# PAGE4_-_SENSORS.net
KiCad netlist of a schematic drawn in Altium Designer
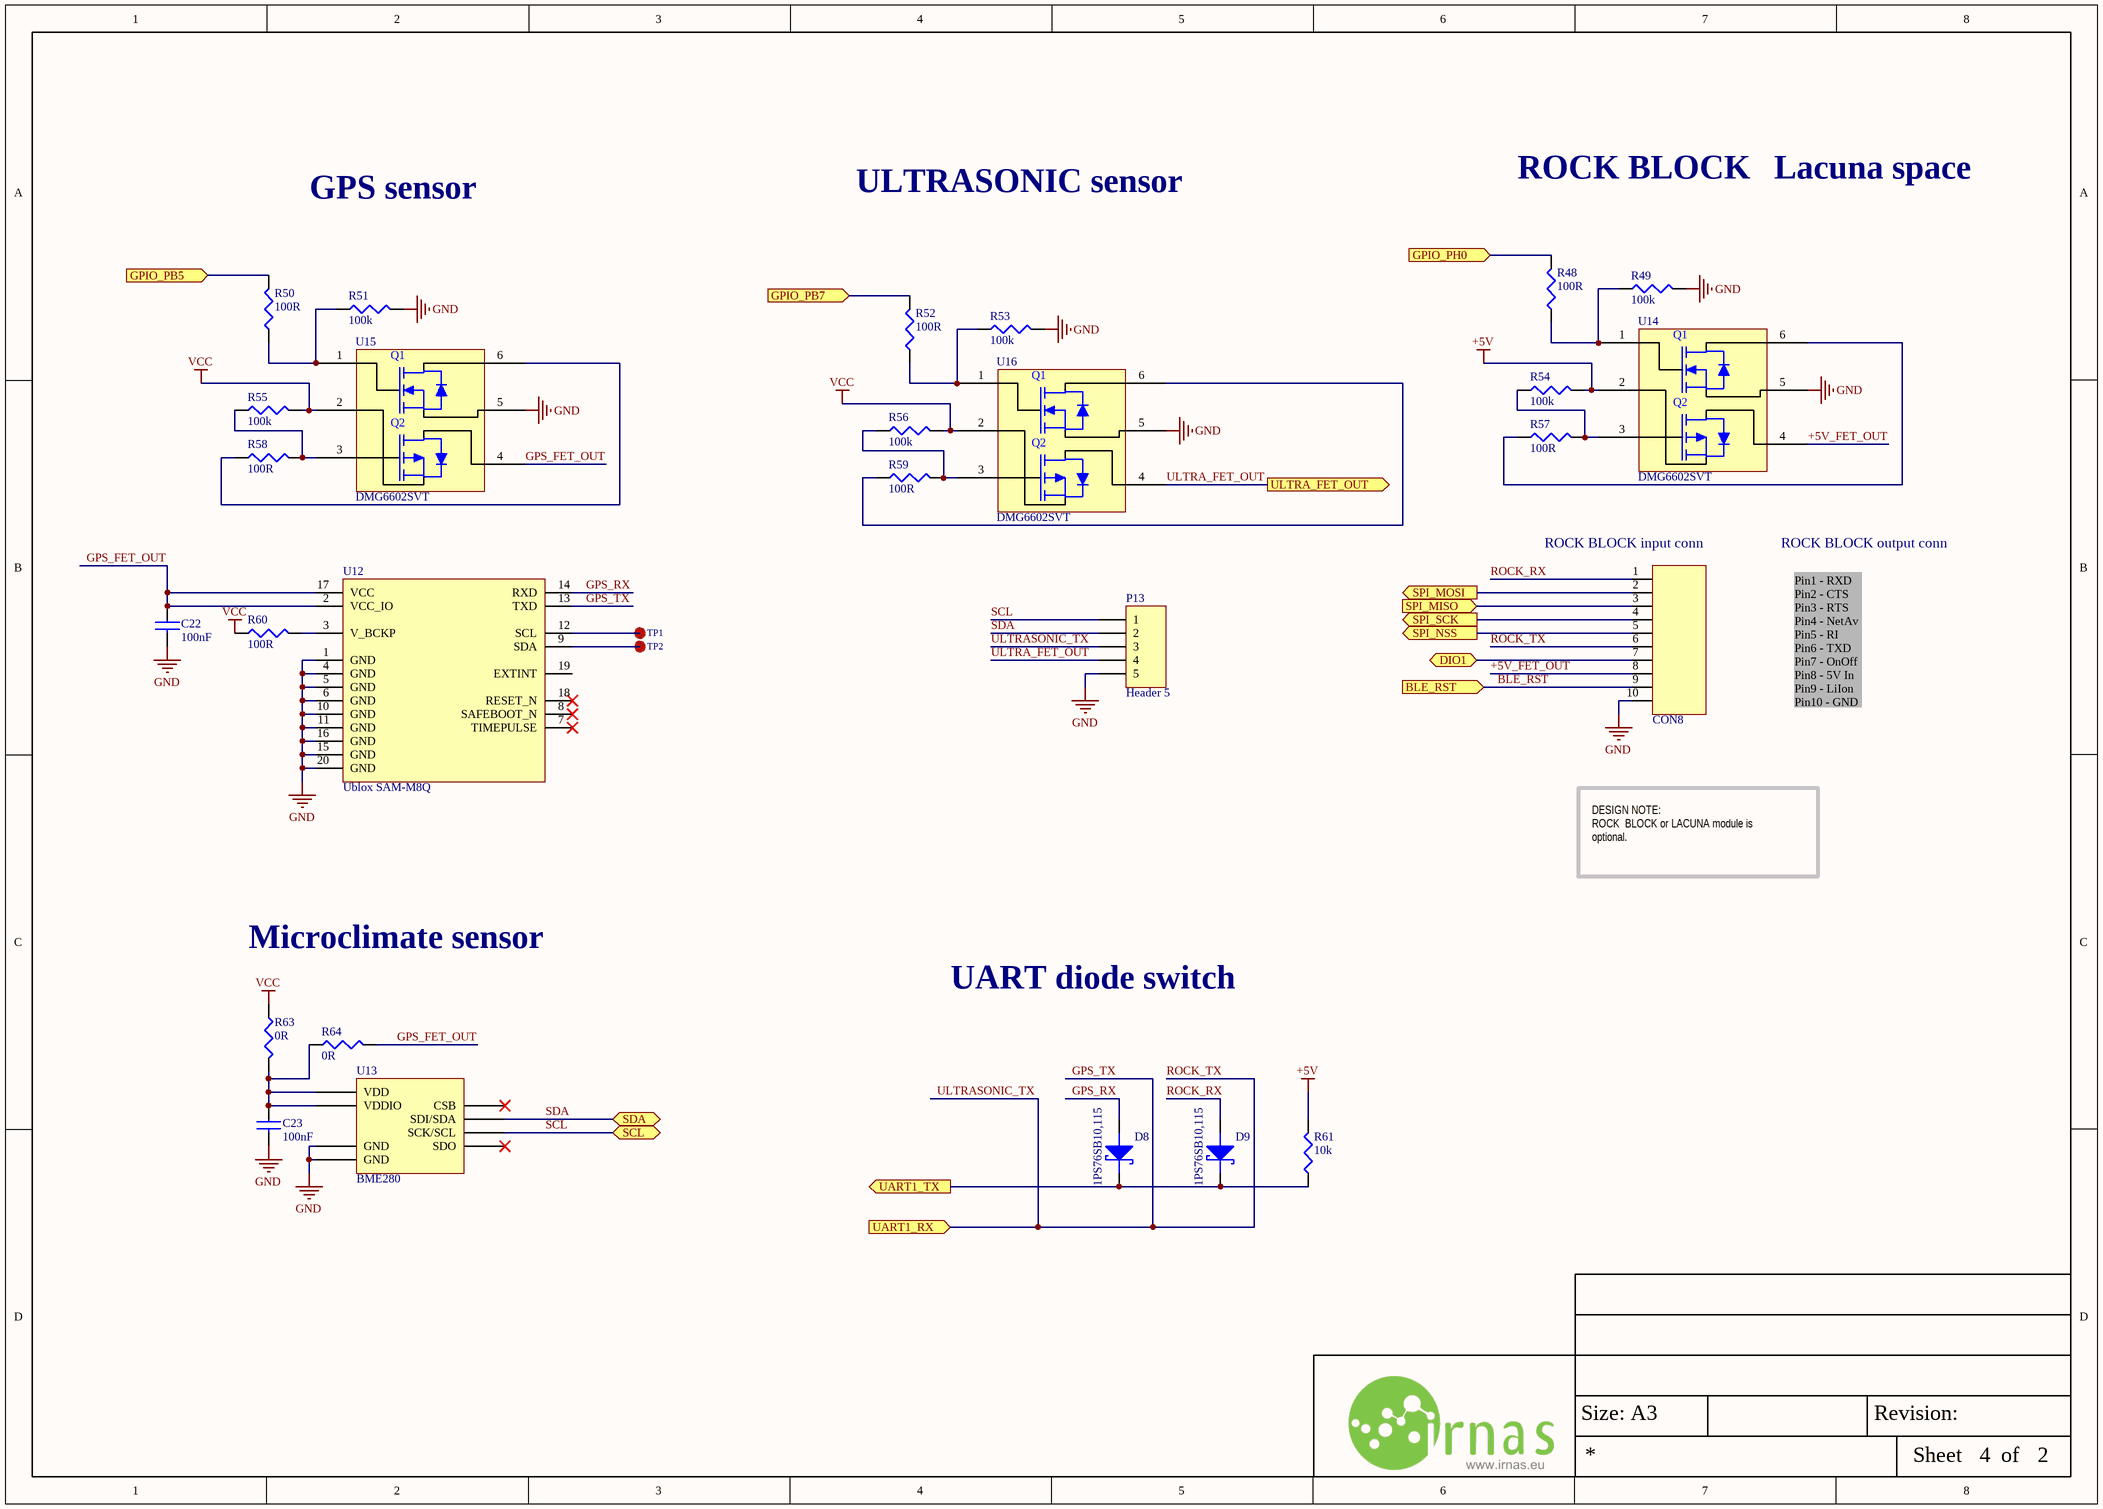
[diagram p0: PAGE4 - SENSORS.SchDoc]

(export (version "E")
  (design (tool "Eeschema 10.0.6"))
  (components
    (comp (ref "C22")
      (value "100nF")
      (footprint "CAP0603")
      (description "MURATA - GRM188R71C104KA01J - CAP, MLCC, X7R, 0.1UF, 16V, 0603")
      (fields
        (field (name "MANUFACTURER") "MURATA")
        (field (name "MANUFACTURER PART NUMBER") "GRM188R71C104KA01J")
      )
      (libsource (lib "Passive") (part "C - 100nF"))
    )
    (comp (ref "C23")
      (value "100nF")
      (footprint "CAP0603")
      (description "MURATA - GRM188R71C104KA01J - CAP, MLCC, X7R, 0.1UF, 16V, 0603")
      (fields
        (field (name "MANUFACTURER") "MURATA")
        (field (name "MANUFACTURER PART NUMBER") "GRM188R71C104KA01J")
      )
      (libsource (lib "Passive") (part "C - 100nF"))
    )
    (comp (ref "CON8")
      (value "53261-1071")
      (footprint "PICOBLADE 10PIN")
      (description "Wire-To-Board Connector, Right Angle, 1.25 mm, 10 Contacts, Header, PicoBlade 53261 Series")
      (libsource (lib "Connectors") (part "PicoBlade 10pin"))
    )
    (comp (ref "D8")
      (value "1PS76SB10,115")
      (footprint "SOD-323")
      (description "Small Signal Schottky Diode, Single, 30 V, 200 mA, 320 mV, 800 mA, 125 °C")
      (libsource (lib "Active") (part "DS - 1PS76SB10,115"))
    )
    (comp (ref "D9")
      (value "1PS76SB10,115")
      (footprint "SOD-323")
      (description "Small Signal Schottky Diode, Single, 30 V, 200 mA, 320 mV, 800 mA, 125 °C")
      (libsource (lib "Active") (part "DS - 1PS76SB10,115"))
    )
    (comp (ref "P13")
      (value "Header 5")
      (footprint "HDR1X5")
      (description "Header, 5-Pin")
      (fields (field (name "PUBLISHER") "Altium Limited"))
      (libsource (lib "Miscellaneous Connectors") (part "Header 5"))
    )
    (comp (ref "R48")
      (value "100R")
      (footprint "RES0603")
      (description "MULTICOMP - MC0063W06031100R - RES, THICK FILM, 100R, 1%, 0.063W, 0603")
      (fields
        (field (name "MANUFACTURER") "MULTICOMP")
        (field (name "MANUFACTURER PART NUMBER") "MC0063W06031100R")
      )
      (libsource (lib "Passive") (part "R - 100R"))
    )
    (comp (ref "R49")
      (value "100k")
      (footprint "RES0603")
      (description "MULTICOMP - MCMR06X104 JTL - RES, CERAMIC, 100K, 5%, 0.1W, 0603")
      (fields
        (field (name "MANUFACTURER") "MULTICOMP")
        (field (name "MANUFACTURER PART NUMBER") "MCMR06X104 JTL")
      )
      (libsource (lib "Passive") (part "R - 100k"))
    )
    (comp (ref "R50")
      (value "100R")
      (footprint "RES0603")
      (description "MULTICOMP - MC0063W06031100R - RES, THICK FILM, 100R, 1%, 0.063W, 0603")
      (fields
        (field (name "MANUFACTURER") "MULTICOMP")
        (field (name "MANUFACTURER PART NUMBER") "MC0063W06031100R")
      )
      (libsource (lib "Passive") (part "R - 100R"))
    )
    (comp (ref "R51")
      (value "100k")
      (footprint "RES0603")
      (description "MULTICOMP - MCMR06X104 JTL - RES, CERAMIC, 100K, 5%, 0.1W, 0603")
      (fields
        (field (name "MANUFACTURER") "MULTICOMP")
        (field (name "MANUFACTURER PART NUMBER") "MCMR06X104 JTL")
      )
      (libsource (lib "Passive") (part "R - 100k"))
    )
    (comp (ref "R52")
      (value "100R")
      (footprint "RES0603")
      (description "MULTICOMP - MC0063W06031100R - RES, THICK FILM, 100R, 1%, 0.063W, 0603")
      (fields
        (field (name "MANUFACTURER") "MULTICOMP")
        (field (name "MANUFACTURER PART NUMBER") "MC0063W06031100R")
      )
      (libsource (lib "Passive") (part "R - 100R"))
    )
    (comp (ref "R53")
      (value "100k")
      (footprint "RES0603")
      (description "MULTICOMP - MCMR06X104 JTL - RES, CERAMIC, 100K, 5%, 0.1W, 0603")
      (fields
        (field (name "MANUFACTURER") "MULTICOMP")
        (field (name "MANUFACTURER PART NUMBER") "MCMR06X104 JTL")
      )
      (libsource (lib "Passive") (part "R - 100k"))
    )
    (comp (ref "R54")
      (value "100k")
      (footprint "RES0603")
      (description "MULTICOMP - MCMR06X104 JTL - RES, CERAMIC, 100K, 5%, 0.1W, 0603")
      (fields
        (field (name "MANUFACTURER") "MULTICOMP")
        (field (name "MANUFACTURER PART NUMBER") "MCMR06X104 JTL")
      )
      (libsource (lib "Passive") (part "R - 100k"))
    )
    (comp (ref "R55")
      (value "100k")
      (footprint "RES0603")
      (description "MULTICOMP - MCMR06X104 JTL - RES, CERAMIC, 100K, 5%, 0.1W, 0603")
      (fields
        (field (name "MANUFACTURER") "MULTICOMP")
        (field (name "MANUFACTURER PART NUMBER") "MCMR06X104 JTL")
      )
      (libsource (lib "Passive") (part "R - 100k"))
    )
    (comp (ref "R56")
      (value "100k")
      (footprint "RES0603")
      (description "MULTICOMP - MCMR06X104 JTL - RES, CERAMIC, 100K, 5%, 0.1W, 0603")
      (fields
        (field (name "MANUFACTURER") "MULTICOMP")
        (field (name "MANUFACTURER PART NUMBER") "MCMR06X104 JTL")
      )
      (libsource (lib "Passive") (part "R - 100k"))
    )
    (comp (ref "R57")
      (value "100R")
      (footprint "RES0603")
      (description "MULTICOMP - MC0063W06031100R - RES, THICK FILM, 100R, 1%, 0.063W, 0603")
      (fields
        (field (name "MANUFACTURER") "MULTICOMP")
        (field (name "MANUFACTURER PART NUMBER") "MC0063W06031100R")
      )
      (libsource (lib "Passive") (part "R - 100R"))
    )
    (comp (ref "R58")
      (value "100R")
      (footprint "RES0603")
      (description "MULTICOMP - MC0063W06031100R - RES, THICK FILM, 100R, 1%, 0.063W, 0603")
      (fields
        (field (name "MANUFACTURER") "MULTICOMP")
        (field (name "MANUFACTURER PART NUMBER") "MC0063W06031100R")
      )
      (libsource (lib "Passive") (part "R - 100R"))
    )
    (comp (ref "R59")
      (value "100R")
      (footprint "RES0603")
      (description "MULTICOMP - MC0063W06031100R - RES, THICK FILM, 100R, 1%, 0.063W, 0603")
      (fields
        (field (name "MANUFACTURER") "MULTICOMP")
        (field (name "MANUFACTURER PART NUMBER") "MC0063W06031100R")
      )
      (libsource (lib "Passive") (part "R - 100R"))
    )
    (comp (ref "R60")
      (value "100R")
      (footprint "RES0603")
      (description "MULTICOMP - MC0063W06031100R - RES, THICK FILM, 100R, 1%, 0.063W, 0603")
      (fields
        (field (name "MANUFACTURER") "MULTICOMP")
        (field (name "MANUFACTURER PART NUMBER") "MC0063W06031100R")
      )
      (libsource (lib "Passive") (part "R - 100R"))
    )
    (comp (ref "R61")
      (value "10k")
      (footprint "RES0603")
      (description "MULTICOMP - MCMR06X103 JTL - RES, CERAMIC, 10K, 5%, 0.1W, 0603")
      (fields
        (field (name "MANUFACTURER") "MULTICOMP")
        (field (name "MANUFACTURER PART NUMBER") "MCMR06X103 JTL")
      )
      (libsource (lib "Passive") (part "R - 10k"))
    )
    (comp (ref "R63")
      (value "0R")
      (footprint "RES0603")
      (description "BOURNS - CR0603-J/-000ELF - RES, THICK FILM, 0R, 5%, 0.1W, 0603")
      (fields
        (field (name "MANUFACTURER") "BOURNS")
        (field (name "MANUFACTURER PART NUMBER") "CR0603-J/-000ELF")
      )
      (libsource (lib "Passive") (part "R - 0R"))
    )
    (comp (ref "R64")
      (value "0R")
      (footprint "RES0603")
      (description "BOURNS - CR0603-J/-000ELF - RES, THICK FILM, 0R, 5%, 0.1W, 0603")
      (fields
        (field (name "MANUFACTURER") "BOURNS")
        (field (name "MANUFACTURER PART NUMBER") "CR0603-J/-000ELF")
      )
      (libsource (lib "Passive") (part "R - 0R"))
    )
    (comp (ref "TP1")
      (value "TestPoint")
      (footprint "Passive:TestPoint:1.2x1.2mm")
      (description "TEST POINT ROUND SMD")
      (libsource (lib "Passive") (part "TestPoint"))
    )
    (comp (ref "TP2")
      (value "TestPoint")
      (footprint "Passive:TestPoint:1.2x1.2mm")
      (description "TEST POINT ROUND SMD")
      (libsource (lib "Passive") (part "TestPoint"))
    )
    (comp (ref "U12")
      (value "Ublox SAM-M8Q")
      (footprint "SAM-M8Q")
      (description "SAM-M8 RF Receiver BeiDou, Galileo, GLONASS, GNSS, GPS -160dBm")
      (fields (field (name "MANUFACTURER") "u-blox") (field (name "MANUFACTURER PART NUMBER") "MAX-M8Q-0"))
      (libsource (lib "Active") (part "RF - UBLOX-SAM-M8Q"))
    )
    (comp (ref "U13")
      (value "BME280")
      (footprint "BME280")
      (description "Humidity Temperature Sensor 0 ~ 100% RH I²C, SPI ±3% 1s Surface Mount")
      (libsource (lib "Active") (part "SEN - BME280"))
    )
    (comp (ref "U14")
      (value "DMG6602SVT")
      (footprint "TSOT26")
      (description "Dual MOSFET, N and P Channel, 3.4 A, 30 V, 0.038 ohm, 10 V, 1 V")
      (libsource (lib "Active") (part "T_M - DMG6602SVT"))
    )
    (comp (ref "U15")
      (value "DMG6602SVT")
      (footprint "TSOT26")
      (description "Dual MOSFET, N and P Channel, 3.4 A, 30 V, 0.038 ohm, 10 V, 1 V")
      (libsource (lib "Active") (part "T_M - DMG6602SVT"))
    )
    (comp (ref "U16")
      (value "DMG6602SVT")
      (footprint "TSOT26")
      (description "Dual MOSFET, N and P Channel, 3.4 A, 30 V, 0.038 ohm, 10 V, 1 V")
      (libsource (lib "Active") (part "T_M - DMG6602SVT"))
    )
  )
  (nets
    (net (code "1") (name "+5V") (class "Default")
      (node (ref "R54") (pin "2") (pinfunction "2_2") (pintype "passive"))
      (node (ref "R61") (pin "2") (pinfunction "2_2") (pintype "passive"))
      (node (ref "U14") (pin "2") (pinfunction "S2_2") (pintype "open_collector"))
    )
    (net (code "2") (name "/+5V_FET_OUT") (class "Default")
      (node (ref "CON8") (pin "8") (pinfunction "8_8") (pintype "passive"))
      (node (ref "U14") (pin "4") (pinfunction "D2_4") (pintype "open_collector"))
    )
    (net (code "3") (name "/BLE_RST") (class "Default")
      (node (ref "CON8") (pin "9") (pinfunction "9_9") (pintype "passive"))
    )
    (net (code "4") (name "/DIO1") (class "Default")
      (node (ref "CON8") (pin "7") (pinfunction "7_7") (pintype "passive"))
    )
    (net (code "5") (name "/GPIO_PB5") (class "Default")
      (node (ref "R50") (pin "2") (pinfunction "2_2") (pintype "passive"))
    )
    (net (code "6") (name "/GPIO_PB7") (class "Default")
      (node (ref "R52") (pin "2") (pinfunction "2_2") (pintype "passive"))
    )
    (net (code "7") (name "/GPIO_PH0") (class "Default")
      (node (ref "R48") (pin "2") (pinfunction "2_2") (pintype "passive"))
    )
    (net (code "8") (name "/GPS_FET_OUT") (class "Default")
      (node (ref "C22") (pin "1") (pinfunction "1_1") (pintype "passive"))
      (node (ref "R64") (pin "2") (pinfunction "2_2") (pintype "passive"))
      (node (ref "U12") (pin "17") (pinfunction "VCC_17") (pintype "passive"))
      (node (ref "U12") (pin "2") (pinfunction "VCC_IO_2") (pintype "passive"))
      (node (ref "U15") (pin "4") (pinfunction "D2_4") (pintype "open_collector"))
    )
    (net (code "9") (name "/GPS_RX") (class "Default")
      (node (ref "D8") (pin "2") (pinfunction "ANODE_2") (pintype "passive"))
      (node (ref "U12") (pin "14") (pinfunction "RXD_14") (pintype "passive"))
    )
    (net (code "10") (name "/GPS_TX") (class "Default")
      (node (ref "CON8") (pin "6") (pinfunction "6_6") (pintype "passive"))
      (node (ref "P13") (pin "3") (pinfunction "3_3") (pintype "passive"))
      (node (ref "U12") (pin "13") (pinfunction "TXD_13") (pintype "passive"))
    )
    (net (code "11") (name "/ROCK_RX") (class "Default")
      (node (ref "CON8") (pin "1") (pinfunction "1_1") (pintype "passive"))
      (node (ref "D9") (pin "2") (pinfunction "ANODE_2") (pintype "passive"))
    )
    (net (code "12") (name "/SCL") (class "Default")
      (node (ref "P13") (pin "1") (pinfunction "1_1") (pintype "passive"))
      (node (ref "U13") (pin "4") (pinfunction "SCK/SCL_4") (pintype "passive"))
    )
    (net (code "13") (name "/SDA") (class "Default")
      (node (ref "P13") (pin "2") (pinfunction "2_2") (pintype "passive"))
      (node (ref "U13") (pin "3") (pinfunction "SDI/SDA_3") (pintype "passive"))
    )
    (net (code "14") (name "/SPI_MISO") (class "Default")
      (node (ref "CON8") (pin "3") (pinfunction "3_3") (pintype "passive"))
    )
    (net (code "15") (name "/SPI_MOSI") (class "Default")
      (node (ref "CON8") (pin "2") (pinfunction "2_2") (pintype "passive"))
    )
    (net (code "16") (name "/SPI_NSS") (class "Default")
      (node (ref "CON8") (pin "5") (pinfunction "5_5") (pintype "passive"))
    )
    (net (code "17") (name "/SPI_SCK") (class "Default")
      (node (ref "CON8") (pin "4") (pinfunction "4_4") (pintype "passive"))
    )
    (net (code "18") (name "/UART1_TX") (class "Default")
      (node (ref "D8") (pin "1") (pinfunction "cathode_1") (pintype "passive"))
      (node (ref "D9") (pin "1") (pinfunction "cathode_1") (pintype "passive"))
      (node (ref "R61") (pin "1") (pinfunction "1_1") (pintype "passive"))
    )
    (net (code "19") (name "/ULTRA_FET_OUT") (class "Default")
      (node (ref "P13") (pin "4") (pinfunction "4_4") (pintype "passive"))
      (node (ref "U16") (pin "4") (pinfunction "D2_4") (pintype "open_collector"))
    )
    (net (code "20") (name "GND") (class "Default")
      (node (ref "C22") (pin "2") (pinfunction "2_2") (pintype "passive"))
      (node (ref "C23") (pin "2") (pinfunction "2_2") (pintype "passive"))
      (node (ref "CON8") (pin "10") (pinfunction "10_10") (pintype "passive"))
      (node (ref "P13") (pin "5") (pinfunction "5_5") (pintype "passive"))
      (node (ref "R49") (pin "2") (pinfunction "2_2") (pintype "passive"))
      (node (ref "R51") (pin "2") (pinfunction "2_2") (pintype "passive"))
      (node (ref "R53") (pin "2") (pinfunction "2_2") (pintype "passive"))
      (node (ref "U12") (pin "1") (pinfunction "GND_1") (pintype "passive"))
      (node (ref "U12") (pin "10") (pinfunction "GND_10") (pintype "passive"))
      (node (ref "U12") (pin "11") (pinfunction "GND_11") (pintype "passive"))
      (node (ref "U12") (pin "15") (pinfunction "GND_15") (pintype "passive"))
      (node (ref "U12") (pin "16") (pinfunction "GND_16") (pintype "passive"))
      (node (ref "U12") (pin "20") (pinfunction "GND_20") (pintype "passive"))
      (node (ref "U12") (pin "4") (pinfunction "GND_4") (pintype "passive"))
      (node (ref "U12") (pin "5") (pinfunction "GND_5") (pintype "passive"))
      (node (ref "U12") (pin "6") (pinfunction "GND_6") (pintype "passive"))
      (node (ref "U13") (pin "1") (pinfunction "GND_1") (pintype "passive"))
      (node (ref "U13") (pin "7") (pinfunction "GND_7") (pintype "passive"))
      (node (ref "U14") (pin "5") (pinfunction "S1_5") (pintype "open_collector"))
      (node (ref "U15") (pin "5") (pinfunction "S1_5") (pintype "open_collector"))
      (node (ref "U16") (pin "5") (pinfunction "S1_5") (pintype "open_collector"))
    )
    (net (code "21") (name "Net-(U12-SCL)") (class "Default")
      (node (ref "TP1") (pin "0") (pinfunction "0_0") (pintype "passive"))
      (node (ref "U12") (pin "12") (pinfunction "SCL_12") (pintype "passive"))
    )
    (net (code "22") (name "Net-(U12-SDA)") (class "Default")
      (node (ref "TP2") (pin "0") (pinfunction "0_0") (pintype "passive"))
      (node (ref "U12") (pin "9") (pinfunction "SDA_9") (pintype "passive"))
    )
    (net (code "23") (name "Net-(U12-V_BCKP)") (class "Default")
      (node (ref "R60") (pin "2") (pinfunction "2_2") (pintype "passive"))
      (node (ref "U12") (pin "3") (pinfunction "V_BCKP_3") (pintype "passive"))
    )
    (net (code "24") (name "Net-(U13-VDD)") (class "Default")
      (node (ref "C23") (pin "1") (pinfunction "1_1") (pintype "passive"))
      (node (ref "R63") (pin "2") (pinfunction "2_2") (pintype "passive"))
      (node (ref "R64") (pin "1") (pinfunction "1_1") (pintype "passive"))
      (node (ref "U13") (pin "6") (pinfunction "VDDIO_6") (pintype "passive"))
      (node (ref "U13") (pin "8") (pinfunction "VDD_8") (pintype "passive"))
    )
    (net (code "25") (name "Net-(U14-D1)") (class "Default")
      (node (ref "R57") (pin "1") (pinfunction "1_1") (pintype "passive"))
      (node (ref "U14") (pin "6") (pinfunction "D1_6") (pintype "open_collector"))
    )
    (net (code "26") (name "Net-(U14-G1)") (class "Default")
      (node (ref "R48") (pin "1") (pinfunction "1_1") (pintype "passive"))
      (node (ref "R49") (pin "1") (pinfunction "1_1") (pintype "passive"))
      (node (ref "U14") (pin "1") (pinfunction "G1_1") (pintype "open_collector"))
    )
    (net (code "27") (name "Net-(U14-G2)") (class "Default")
      (node (ref "R54") (pin "1") (pinfunction "1_1") (pintype "passive"))
      (node (ref "R57") (pin "2") (pinfunction "2_2") (pintype "passive"))
      (node (ref "U14") (pin "3") (pinfunction "G2_3") (pintype "open_collector"))
    )
    (net (code "28") (name "Net-(U15-D1)") (class "Default")
      (node (ref "R58") (pin "1") (pinfunction "1_1") (pintype "passive"))
      (node (ref "U15") (pin "6") (pinfunction "D1_6") (pintype "open_collector"))
    )
    (net (code "29") (name "Net-(U15-G1)") (class "Default")
      (node (ref "R50") (pin "1") (pinfunction "1_1") (pintype "passive"))
      (node (ref "R51") (pin "1") (pinfunction "1_1") (pintype "passive"))
      (node (ref "U15") (pin "1") (pinfunction "G1_1") (pintype "open_collector"))
    )
    (net (code "30") (name "Net-(U15-G2)") (class "Default")
      (node (ref "R55") (pin "1") (pinfunction "1_1") (pintype "passive"))
      (node (ref "R58") (pin "2") (pinfunction "2_2") (pintype "passive"))
      (node (ref "U15") (pin "3") (pinfunction "G2_3") (pintype "open_collector"))
    )
    (net (code "31") (name "Net-(U16-D1)") (class "Default")
      (node (ref "R59") (pin "1") (pinfunction "1_1") (pintype "passive"))
      (node (ref "U16") (pin "6") (pinfunction "D1_6") (pintype "open_collector"))
    )
    (net (code "32") (name "Net-(U16-G1)") (class "Default")
      (node (ref "R52") (pin "1") (pinfunction "1_1") (pintype "passive"))
      (node (ref "R53") (pin "1") (pinfunction "1_1") (pintype "passive"))
      (node (ref "U16") (pin "1") (pinfunction "G1_1") (pintype "open_collector"))
    )
    (net (code "33") (name "Net-(U16-G2)") (class "Default")
      (node (ref "R56") (pin "1") (pinfunction "1_1") (pintype "passive"))
      (node (ref "R59") (pin "2") (pinfunction "2_2") (pintype "passive"))
      (node (ref "U16") (pin "3") (pinfunction "G2_3") (pintype "open_collector"))
    )
    (net (code "34") (name "VCC") (class "Default")
      (node (ref "R55") (pin "2") (pinfunction "2_2") (pintype "passive"))
      (node (ref "R56") (pin "2") (pinfunction "2_2") (pintype "passive"))
      (node (ref "R60") (pin "1") (pinfunction "1_1") (pintype "passive"))
      (node (ref "R63") (pin "1") (pinfunction "1_1") (pintype "passive"))
      (node (ref "U15") (pin "2") (pinfunction "S2_2") (pintype "open_collector"))
      (node (ref "U16") (pin "2") (pinfunction "S2_2") (pintype "open_collector"))
    )
    (net (code "35") (name "unconnected-(U12-EXTINT-Pad19)") (class "Default")
      (node (ref "U12") (pin "19") (pinfunction "EXTINT_19") (pintype "passive"))
    )
    (net (code "36") (name "unconnected-(U12-RESET_N-Pad18)") (class "Default")
      (node (ref "U12") (pin "18") (pinfunction "RESET_N_18") (pintype "passive+no_connect"))
    )
    (net (code "37") (name "unconnected-(U12-SAFEBOOT_N-Pad8)") (class "Default")
      (node (ref "U12") (pin "8") (pinfunction "SAFEBOOT_N_8") (pintype "passive+no_connect"))
    )
    (net (code "38") (name "unconnected-(U12-TIMEPULSE-Pad7)") (class "Default")
      (node (ref "U12") (pin "7") (pinfunction "TIMEPULSE_7") (pintype "passive+no_connect"))
    )
    (net (code "39") (name "unconnected-(U13-CSB-Pad2)") (class "Default")
      (node (ref "U13") (pin "2") (pinfunction "CSB_2") (pintype "passive+no_connect"))
    )
    (net (code "40") (name "unconnected-(U13-SDO-Pad5)") (class "Default")
      (node (ref "U13") (pin "5") (pinfunction "SDO_5") (pintype "passive+no_connect"))
    )
  )
)
